# gyro_board.net
KiCad netlist of a schematic drawn in EAGLE
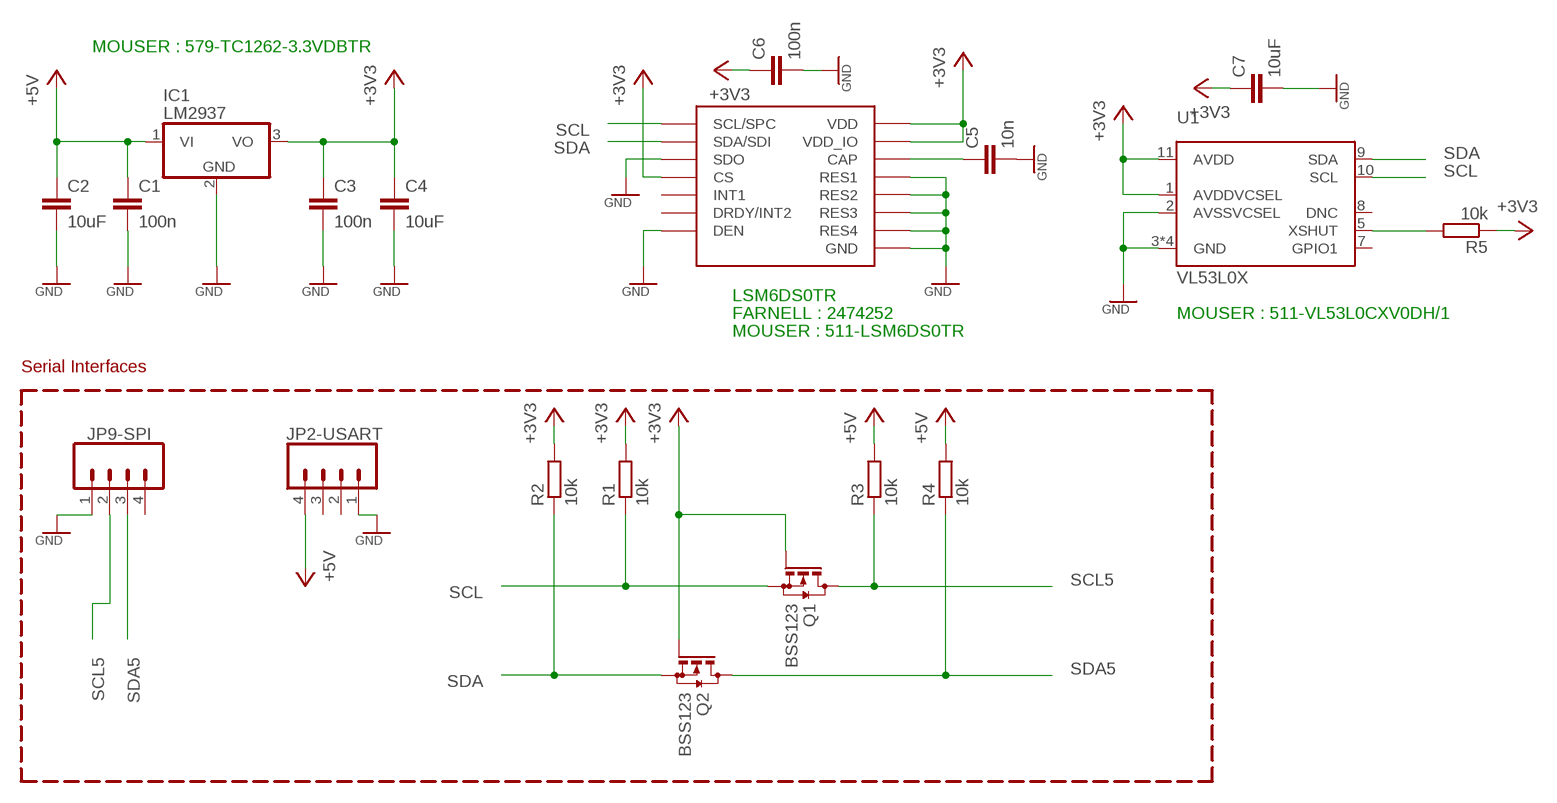
[diagram p0: schematic, sheet 1]

(export (version "E")
  (design (tool "Eeschema 10.0.6"))
  (components
    (comp (ref "C1")
      (value "100n")
      (footprint "eagle-import:C0805K")
      (libsource (lib "eagle-import") (part "C-EUC0805K"))
    )
    (comp (ref "C2")
      (value "10uF")
      (footprint "eagle-import:C0805K")
      (libsource (lib "eagle-import") (part "C-EUC0805K"))
    )
    (comp (ref "C3")
      (value "100n")
      (footprint "eagle-import:C0805K")
      (libsource (lib "eagle-import") (part "C-EUC0805K"))
    )
    (comp (ref "C4")
      (value "10uF")
      (footprint "eagle-import:C0805K")
      (libsource (lib "eagle-import") (part "C-EUC0805K"))
    )
    (comp (ref "C5")
      (value "10n")
      (footprint "eagle-import:C0805K")
      (libsource (lib "eagle-import") (part "C-EUC0805K"))
    )
    (comp (ref "C6")
      (value "100n")
      (footprint "eagle-import:C0805K")
      (libsource (lib "eagle-import") (part "C-EUC0805K"))
    )
    (comp (ref "C7")
      (value "10uF")
      (footprint "eagle-import:C0805K")
      (libsource (lib "eagle-import") (part "C-EUC0805K"))
    )
    (comp (ref "IC1")
      (value "LM2937")
      (footprint "eagle-import:TO263-3")
      (libsource (lib "eagle-import") (part "LM2937"))
    )
    (comp (ref "JP2-USART")
      (value "M04PTH")
      (footprint "eagle-import:1X04")
      (libsource (lib "eagle-import") (part "M04PTH"))
    )
    (comp (ref "JP9-SPI")
      (value "M04PTH")
      (footprint "eagle-import:1X04")
      (libsource (lib "eagle-import") (part "M04PTH"))
    )
    (comp (ref "LSM6DS0TR")
      (value "L3GD20H")
      (footprint "eagle-import:LGA16L")
      (libsource (lib "eagle-import") (part "L3GD20H"))
    )
    (comp (ref "Q1")
      (value "BSS123")
      (footprint "eagle-import:SOT23")
      (libsource (lib "eagle-import") (part "BSS123"))
    )
    (comp (ref "Q2")
      (value "BSS123")
      (footprint "eagle-import:SOT23")
      (libsource (lib "eagle-import") (part "BSS123"))
    )
    (comp (ref "R1")
      (value "10k")
      (footprint "eagle-import:R0805")
      (libsource (lib "eagle-import") (part "R-EU_R0805"))
    )
    (comp (ref "R2")
      (value "10k")
      (footprint "eagle-import:R0805")
      (libsource (lib "eagle-import") (part "R-EU_R0805"))
    )
    (comp (ref "R3")
      (value "10k")
      (footprint "eagle-import:R0805")
      (libsource (lib "eagle-import") (part "R-EU_R0805"))
    )
    (comp (ref "R4")
      (value "10k")
      (footprint "eagle-import:R0805")
      (libsource (lib "eagle-import") (part "R-EU_R0805"))
    )
    (comp (ref "R5")
      (value "10k")
      (footprint "eagle-import:R0805")
      (libsource (lib "eagle-import") (part "R-EU_R0805"))
    )
    (comp (ref "U1")
      (value "VL53L0X")
      (footprint "eagle-import:VL53L0X")
      (libsource (lib "eagle-import") (part "VL53L0X"))
    )
  )
  (nets
    (net (code "1") (name "+3V3") (class "Default")
      (node (ref "C3") (pin "1") (pinfunction "1_1") (pintype "passive"))
      (node (ref "C4") (pin "1") (pinfunction "1_1") (pintype "passive"))
      (node (ref "C6") (pin "1") (pinfunction "1_1") (pintype "passive"))
      (node (ref "C7") (pin "1") (pinfunction "1_1") (pintype "passive"))
      (node (ref "IC1") (pin "3") (pinfunction "VO_3") (pintype "passive"))
      (node (ref "LSM6DS0TR") (pin "P$1") (pinfunction "VDD_IO_P$1") (pintype "power_in"))
      (node (ref "LSM6DS0TR") (pin "P$16") (pinfunction "VDD_P$16") (pintype "power_in"))
      (node (ref "LSM6DS0TR") (pin "P$5") (pinfunction "CS_P$5") (pintype "bidirectional"))
      (node (ref "Q1") (pin "1") (pinfunction "G_1") (pintype "passive"))
      (node (ref "Q2") (pin "1") (pinfunction "G_1") (pintype "passive"))
      (node (ref "R1") (pin "2") (pinfunction "2_2") (pintype "passive"))
      (node (ref "R2") (pin "2") (pinfunction "2_2") (pintype "passive"))
      (node (ref "R5") (pin "1") (pinfunction "1_1") (pintype "passive"))
      (node (ref "U1") (pin "1") (pinfunction "AVDDVCSEL_1") (pintype "bidirectional"))
      (node (ref "U1") (pin "11") (pinfunction "AVDD_11") (pintype "bidirectional"))
    )
    (net (code "2") (name "+5V") (class "Default")
      (node (ref "C1") (pin "1") (pinfunction "1_1") (pintype "passive"))
      (node (ref "C2") (pin "1") (pinfunction "1_1") (pintype "passive"))
      (node (ref "IC1") (pin "1") (pinfunction "VI_1") (pintype "input"))
      (node (ref "JP2-USART") (pin "4") (pinfunction "4_4") (pintype "passive"))
      (node (ref "R3") (pin "2") (pinfunction "2_2") (pintype "passive"))
      (node (ref "R4") (pin "2") (pinfunction "2_2") (pintype "passive"))
    )
    (net (code "3") (name "/SCL") (class "Default")
      (node (ref "LSM6DS0TR") (pin "P$2") (pinfunction "SCL/SPC_P$2") (pintype "bidirectional"))
      (node (ref "Q1") (pin "2") (pinfunction "S_2") (pintype "passive"))
      (node (ref "R1") (pin "1") (pinfunction "1_1") (pintype "passive"))
      (node (ref "U1") (pin "10") (pinfunction "SCL_10") (pintype "bidirectional"))
    )
    (net (code "4") (name "/SCL5") (class "Default")
      (node (ref "JP9-SPI") (pin "2") (pinfunction "2_2") (pintype "passive"))
      (node (ref "Q1") (pin "3") (pinfunction "D_3") (pintype "passive"))
      (node (ref "R3") (pin "1") (pinfunction "1_1") (pintype "passive"))
    )
    (net (code "5") (name "/SDA") (class "Default")
      (node (ref "LSM6DS0TR") (pin "P$3") (pinfunction "SDA/SDI_P$3") (pintype "bidirectional"))
      (node (ref "Q2") (pin "2") (pinfunction "S_2") (pintype "passive"))
      (node (ref "R2") (pin "1") (pinfunction "1_1") (pintype "passive"))
      (node (ref "U1") (pin "9") (pinfunction "SDA_9") (pintype "bidirectional"))
    )
    (net (code "6") (name "/SDA5") (class "Default")
      (node (ref "JP9-SPI") (pin "3") (pinfunction "3_3") (pintype "passive"))
      (node (ref "Q2") (pin "3") (pinfunction "D_3") (pintype "passive"))
      (node (ref "R4") (pin "1") (pinfunction "1_1") (pintype "passive"))
    )
    (net (code "7") (name "GND") (class "Default")
      (node (ref "C1") (pin "2") (pinfunction "2_2") (pintype "passive"))
      (node (ref "C2") (pin "2") (pinfunction "2_2") (pintype "passive"))
      (node (ref "C3") (pin "2") (pinfunction "2_2") (pintype "passive"))
      (node (ref "C4") (pin "2") (pinfunction "2_2") (pintype "passive"))
      (node (ref "C5") (pin "2") (pinfunction "2_2") (pintype "passive"))
      (node (ref "C6") (pin "2") (pinfunction "2_2") (pintype "passive"))
      (node (ref "C7") (pin "2") (pinfunction "2_2") (pintype "passive"))
      (node (ref "IC1") (pin "2") (pinfunction "GND_2") (pintype "passive"))
      (node (ref "JP2-USART") (pin "1") (pinfunction "1_1") (pintype "passive"))
      (node (ref "JP9-SPI") (pin "1") (pinfunction "1_1") (pintype "passive"))
      (node (ref "LSM6DS0TR") (pin "P$10") (pinfunction "RES2_P$10") (pintype "bidirectional"))
      (node (ref "LSM6DS0TR") (pin "P$11") (pinfunction "RES3_P$11") (pintype "bidirectional"))
      (node (ref "LSM6DS0TR") (pin "P$12") (pinfunction "GND_P$12") (pintype "power_in"))
      (node (ref "LSM6DS0TR") (pin "P$13") (pinfunction "GND_P$13") (pintype "power_in"))
      (node (ref "LSM6DS0TR") (pin "P$15") (pinfunction "RES4_P$15") (pintype "bidirectional"))
      (node (ref "LSM6DS0TR") (pin "P$4") (pinfunction "SDO_P$4") (pintype "bidirectional"))
      (node (ref "LSM6DS0TR") (pin "P$8") (pinfunction "DEN_P$8") (pintype "bidirectional"))
      (node (ref "LSM6DS0TR") (pin "P$9") (pinfunction "RES1_P$9") (pintype "bidirectional"))
      (node (ref "U1") (pin "12") (pinfunction "GND_12") (pintype "bidirectional"))
      (node (ref "U1") (pin "2") (pinfunction "AVSSVCSEL_2") (pintype "bidirectional"))
      (node (ref "U1") (pin "3") (pinfunction "GND_3") (pintype "bidirectional"))
      (node (ref "U1") (pin "4") (pinfunction "GND_4") (pintype "bidirectional"))
      (node (ref "U1") (pin "6") (pinfunction "GND_6") (pintype "bidirectional"))
    )
    (net (code "8") (name "Net-(LSM6DS0TR-CAP)") (class "Default")
      (node (ref "C5") (pin "1") (pinfunction "1_1") (pintype "passive"))
      (node (ref "LSM6DS0TR") (pin "P$14") (pinfunction "CAP_P$14") (pintype "bidirectional"))
    )
    (net (code "9") (name "Net-(U1-XSHUT)") (class "Default")
      (node (ref "R5") (pin "2") (pinfunction "2_2") (pintype "passive"))
      (node (ref "U1") (pin "5") (pinfunction "XSHUT_5") (pintype "bidirectional"))
    )
    (net (code "10") (name "unconnected-(JP2-USART-Pad2)") (class "Default")
      (node (ref "JP2-USART") (pin "2") (pinfunction "2_2") (pintype "passive"))
    )
    (net (code "11") (name "unconnected-(JP2-USART-Pad3)") (class "Default")
      (node (ref "JP2-USART") (pin "3") (pinfunction "3_3") (pintype "passive"))
    )
    (net (code "12") (name "unconnected-(JP9-SPI-Pad4)") (class "Default")
      (node (ref "JP9-SPI") (pin "4") (pinfunction "4_4") (pintype "passive"))
    )
    (net (code "13") (name "unconnected-(LSM6DS0TR-DRDY{slash}INT2-PadP$6)") (class "Default")
      (node (ref "LSM6DS0TR") (pin "P$6") (pinfunction "DRDY/INT2_P$6") (pintype "bidirectional"))
    )
    (net (code "14") (name "unconnected-(LSM6DS0TR-INT1-PadP$7)") (class "Default")
      (node (ref "LSM6DS0TR") (pin "P$7") (pinfunction "INT1_P$7") (pintype "bidirectional"))
    )
    (net (code "15") (name "unconnected-(U1-DNC-Pad8)") (class "Default")
      (node (ref "U1") (pin "8") (pinfunction "DNC_8") (pintype "bidirectional"))
    )
    (net (code "16") (name "unconnected-(U1-GPIO1-Pad7)") (class "Default")
      (node (ref "U1") (pin "7") (pinfunction "GPIO1_7") (pintype "bidirectional"))
    )
  )
)
